# panneau_sheet.net
KiCad netlist of a schematic drawn in Altium Designer
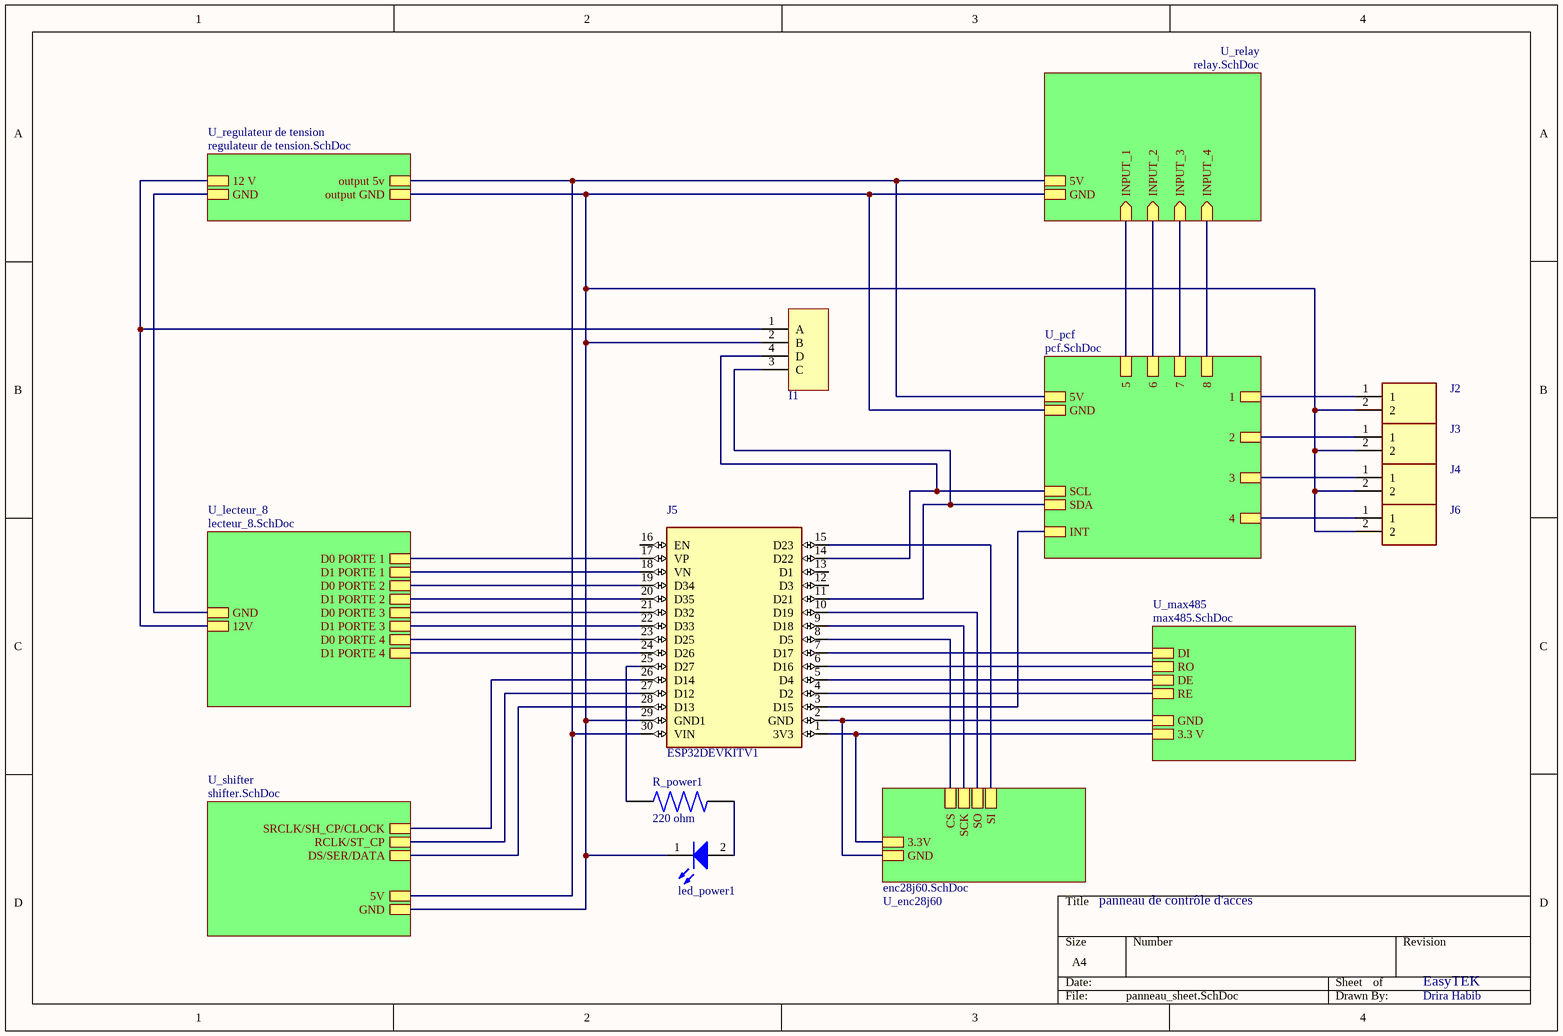
[diagram p0: panneau_sheet.SchDoc]

(export (version "E")
  (design (tool "Eeschema 10.0.6"))
  (components
    (comp (ref "I1")
      (value "Header 4")
      (footprint "JST_4_PIN")
      (libsource (lib "Custom_Component") (part "Connector_4Pin"))
    )
    (comp (ref "J2")
      (value "1546215-2")
      (footprint "SamacSys:15462152")
      (description "Connector")
      (fields (field (name "MOUSER PART NUMBER") "571-1546215-2"))
      (libsource (lib "*") (part "1546215-2"))
    )
    (comp (ref "J3")
      (value "1546215-2")
      (footprint "SamacSys:15462152")
      (description "Connector")
      (fields (field (name "MOUSER PART NUMBER") "571-1546215-2"))
      (libsource (lib "*") (part "1546215-2"))
    )
    (comp (ref "J4")
      (value "1546215-2")
      (footprint "SamacSys:15462152")
      (description "Connector")
      (fields (field (name "MOUSER PART NUMBER") "571-1546215-2"))
      (libsource (lib "*") (part "1546215-2"))
    )
    (comp (ref "J5")
      (value "ESP32DEVKITV1")
      (footprint "ESP32-DEVKITV1_3D")
      (fields (field (name "MF") "Do it") (field (name "MP") "ESP32 DEVKIT V1"))
      (libsource (lib "SchlibBruno") (part "ESP32DEVKITV1"))
    )
    (comp (ref "J6")
      (value "1546215-2")
      (footprint "SamacSys:15462152")
      (description "Connector")
      (fields (field (name "MOUSER PART NUMBER") "571-1546215-2"))
      (libsource (lib "*") (part "1546215-2"))
    )
    (comp (ref "led_power1")
      (value "Infrared, 1.5V, 35°")
      (footprint "WL-TIRW_D5.8H8.6")
      (description "WL-TIRW THT Infrared Round Waterclear, D5.8 x H8.6mm, 85mW/sr, Infrared, 1.5V, 35°")
      (fields
        (field (name "MANUFACTURER PART NUMBER") "15400585A3590")
        (field (name "MANUFACTURER") "Wurth Elektronik")
      )
      (libsource (lib "controlpannel") (part "15400585A3590"))
    )
    (comp (ref "R_power1")
      (value "220 ohm")
      (footprint "RES_ERA2APB221X")
      (fields (field (name "MP") "ERA2APB221X"))
      (libsource (lib "controlpannel") (part "ERA2APB221X"))
    )
  )
  (nets
    (net (code "1") (name "/1") (class "Default")
      (node (ref "J2") (pin "1") (pinfunction "1_1") (pintype "passive"))
    )
    (net (code "2") (name "/2") (class "Default")
      (node (ref "J3") (pin "1") (pinfunction "1_1") (pintype "passive"))
    )
    (net (code "3") (name "/3") (class "Default")
      (node (ref "J4") (pin "1") (pinfunction "1_1") (pintype "passive"))
    )
    (net (code "4") (name "/3.3 V") (class "Default")
      (node (ref "J5") (pin "1") (pinfunction "3V3_1") (pintype "bidirectional"))
    )
    (net (code "5") (name "/4") (class "Default")
      (node (ref "J6") (pin "1") (pinfunction "1_1") (pintype "passive"))
    )
    (net (code "7") (name "/5V") (class "Default")
      (node (ref "J5") (pin "30") (pinfunction "VIN_30") (pintype "bidirectional"))
    )
    (net (code "11") (name "/12 V") (class "Default")
      (node (ref "I1") (pin "1") (pinfunction "A_1") (pintype "passive"))
    )
    (net (code "12") (name "/CS") (class "Default")
      (node (ref "J5") (pin "8") (pinfunction "D5_8") (pintype "bidirectional"))
    )
    (net (code "13") (name "/D0 PORTE 1") (class "Default")
      (node (ref "J5") (pin "17") (pinfunction "VP_17") (pintype "bidirectional"))
    )
    (net (code "14") (name "/D0 PORTE 2") (class "Default")
      (node (ref "J5") (pin "19") (pinfunction "D34_19") (pintype "bidirectional"))
    )
    (net (code "15") (name "/D0 PORTE 3") (class "Default")
      (node (ref "J5") (pin "21") (pinfunction "D32_21") (pintype "bidirectional"))
    )
    (net (code "16") (name "/D0 PORTE 4") (class "Default")
      (node (ref "J5") (pin "23") (pinfunction "D25_23") (pintype "bidirectional"))
    )
    (net (code "17") (name "/D1 PORTE 1") (class "Default")
      (node (ref "J5") (pin "18") (pinfunction "VN_18") (pintype "bidirectional"))
    )
    (net (code "18") (name "/D1 PORTE 2") (class "Default")
      (node (ref "J5") (pin "20") (pinfunction "D35_20") (pintype "bidirectional"))
    )
    (net (code "19") (name "/D1 PORTE 3") (class "Default")
      (node (ref "J5") (pin "22") (pinfunction "D33_22") (pintype "bidirectional"))
    )
    (net (code "20") (name "/D1 PORTE 4") (class "Default")
      (node (ref "J5") (pin "24") (pinfunction "D26_24") (pintype "bidirectional"))
    )
    (net (code "21") (name "/DE") (class "Default")
      (node (ref "J5") (pin "5") (pinfunction "D4_5") (pintype "bidirectional"))
    )
    (net (code "22") (name "/DI") (class "Default")
      (node (ref "J5") (pin "7") (pinfunction "D17_7") (pintype "bidirectional"))
    )
    (net (code "23") (name "/DS{slash}SER{slash}DATA") (class "Default")
      (node (ref "J5") (pin "28") (pinfunction "D13_28") (pintype "bidirectional"))
    )
    (net (code "25") (name "/GND_1") (class "Default")
      (node (ref "J5") (pin "2") (pinfunction "GND_2") (pintype "bidirectional"))
    )
    (net (code "26") (name "/GND_2") (class "Default")
      (node (ref "I1") (pin "2") (pinfunction "B_2") (pintype "passive"))
      (node (ref "J2") (pin "2") (pinfunction "2_2") (pintype "passive"))
      (node (ref "J3") (pin "2") (pinfunction "2_2") (pintype "passive"))
      (node (ref "J4") (pin "2") (pinfunction "2_2") (pintype "passive"))
      (node (ref "J5") (pin "29") (pinfunction "GND1_29") (pintype "bidirectional"))
      (node (ref "J6") (pin "2") (pinfunction "2_2") (pintype "passive"))
      (node (ref "led_power1") (pin "1") (pinfunction "K_1") (pintype "passive"))
    )
    (net (code "27") (name "/INT") (class "Default")
      (node (ref "J5") (pin "3") (pinfunction "D15_3") (pintype "bidirectional"))
    )
    (net (code "28") (name "/RCLK{slash}ST_CP") (class "Default")
      (node (ref "J5") (pin "27") (pinfunction "D12_27") (pintype "bidirectional"))
    )
    (net (code "29") (name "/RE") (class "Default")
      (node (ref "J5") (pin "4") (pinfunction "D2_4") (pintype "bidirectional"))
    )
    (net (code "30") (name "/RO") (class "Default")
      (node (ref "J5") (pin "6") (pinfunction "D16_6") (pintype "bidirectional"))
    )
    (net (code "31") (name "/SCK") (class "Default")
      (node (ref "J5") (pin "9") (pinfunction "D18_9") (pintype "bidirectional"))
    )
    (net (code "32") (name "/SCL") (class "Default")
      (node (ref "I1") (pin "4") (pinfunction "D_4") (pintype "passive"))
      (node (ref "J5") (pin "14") (pinfunction "D22_14") (pintype "bidirectional"))
    )
    (net (code "33") (name "/SDA") (class "Default")
      (node (ref "I1") (pin "3") (pinfunction "C_3") (pintype "passive"))
      (node (ref "J5") (pin "11") (pinfunction "D21_11") (pintype "bidirectional"))
    )
    (net (code "34") (name "/SI") (class "Default")
      (node (ref "J5") (pin "15") (pinfunction "D23_15") (pintype "bidirectional"))
    )
    (net (code "35") (name "/SO") (class "Default")
      (node (ref "J5") (pin "10") (pinfunction "D19_10") (pintype "bidirectional"))
    )
    (net (code "36") (name "/SRCLK{slash}SH_CP{slash}CLOCK") (class "Default")
      (node (ref "J5") (pin "26") (pinfunction "D14_26") (pintype "bidirectional"))
    )
    (net (code "37") (name "Net-(J5-D27)") (class "Default")
      (node (ref "J5") (pin "25") (pinfunction "D27_25") (pintype "bidirectional"))
      (node (ref "R_power1") (pin "1") (pinfunction "1_1") (pintype "passive"))
    )
    (net (code "38") (name "Net-(led_power1-A)") (class "Default")
      (node (ref "R_power1") (pin "2") (pinfunction "2_2") (pintype "passive"))
      (node (ref "led_power1") (pin "2") (pinfunction "A_2") (pintype "passive"))
    )
    (net (code "39") (name "unconnected-(J5-D1-Pad13)") (class "Default")
      (node (ref "J5") (pin "13") (pinfunction "D1_13") (pintype "bidirectional"))
    )
    (net (code "40") (name "unconnected-(J5-D3-Pad12)") (class "Default")
      (node (ref "J5") (pin "12") (pinfunction "D3_12") (pintype "bidirectional"))
    )
    (net (code "41") (name "unconnected-(J5-EN-Pad16)") (class "Default")
      (node (ref "J5") (pin "16") (pinfunction "EN_16") (pintype "bidirectional"))
    )
  )
)
